# design.net
KiCad netlist of a schematic drawn in Altium Designer
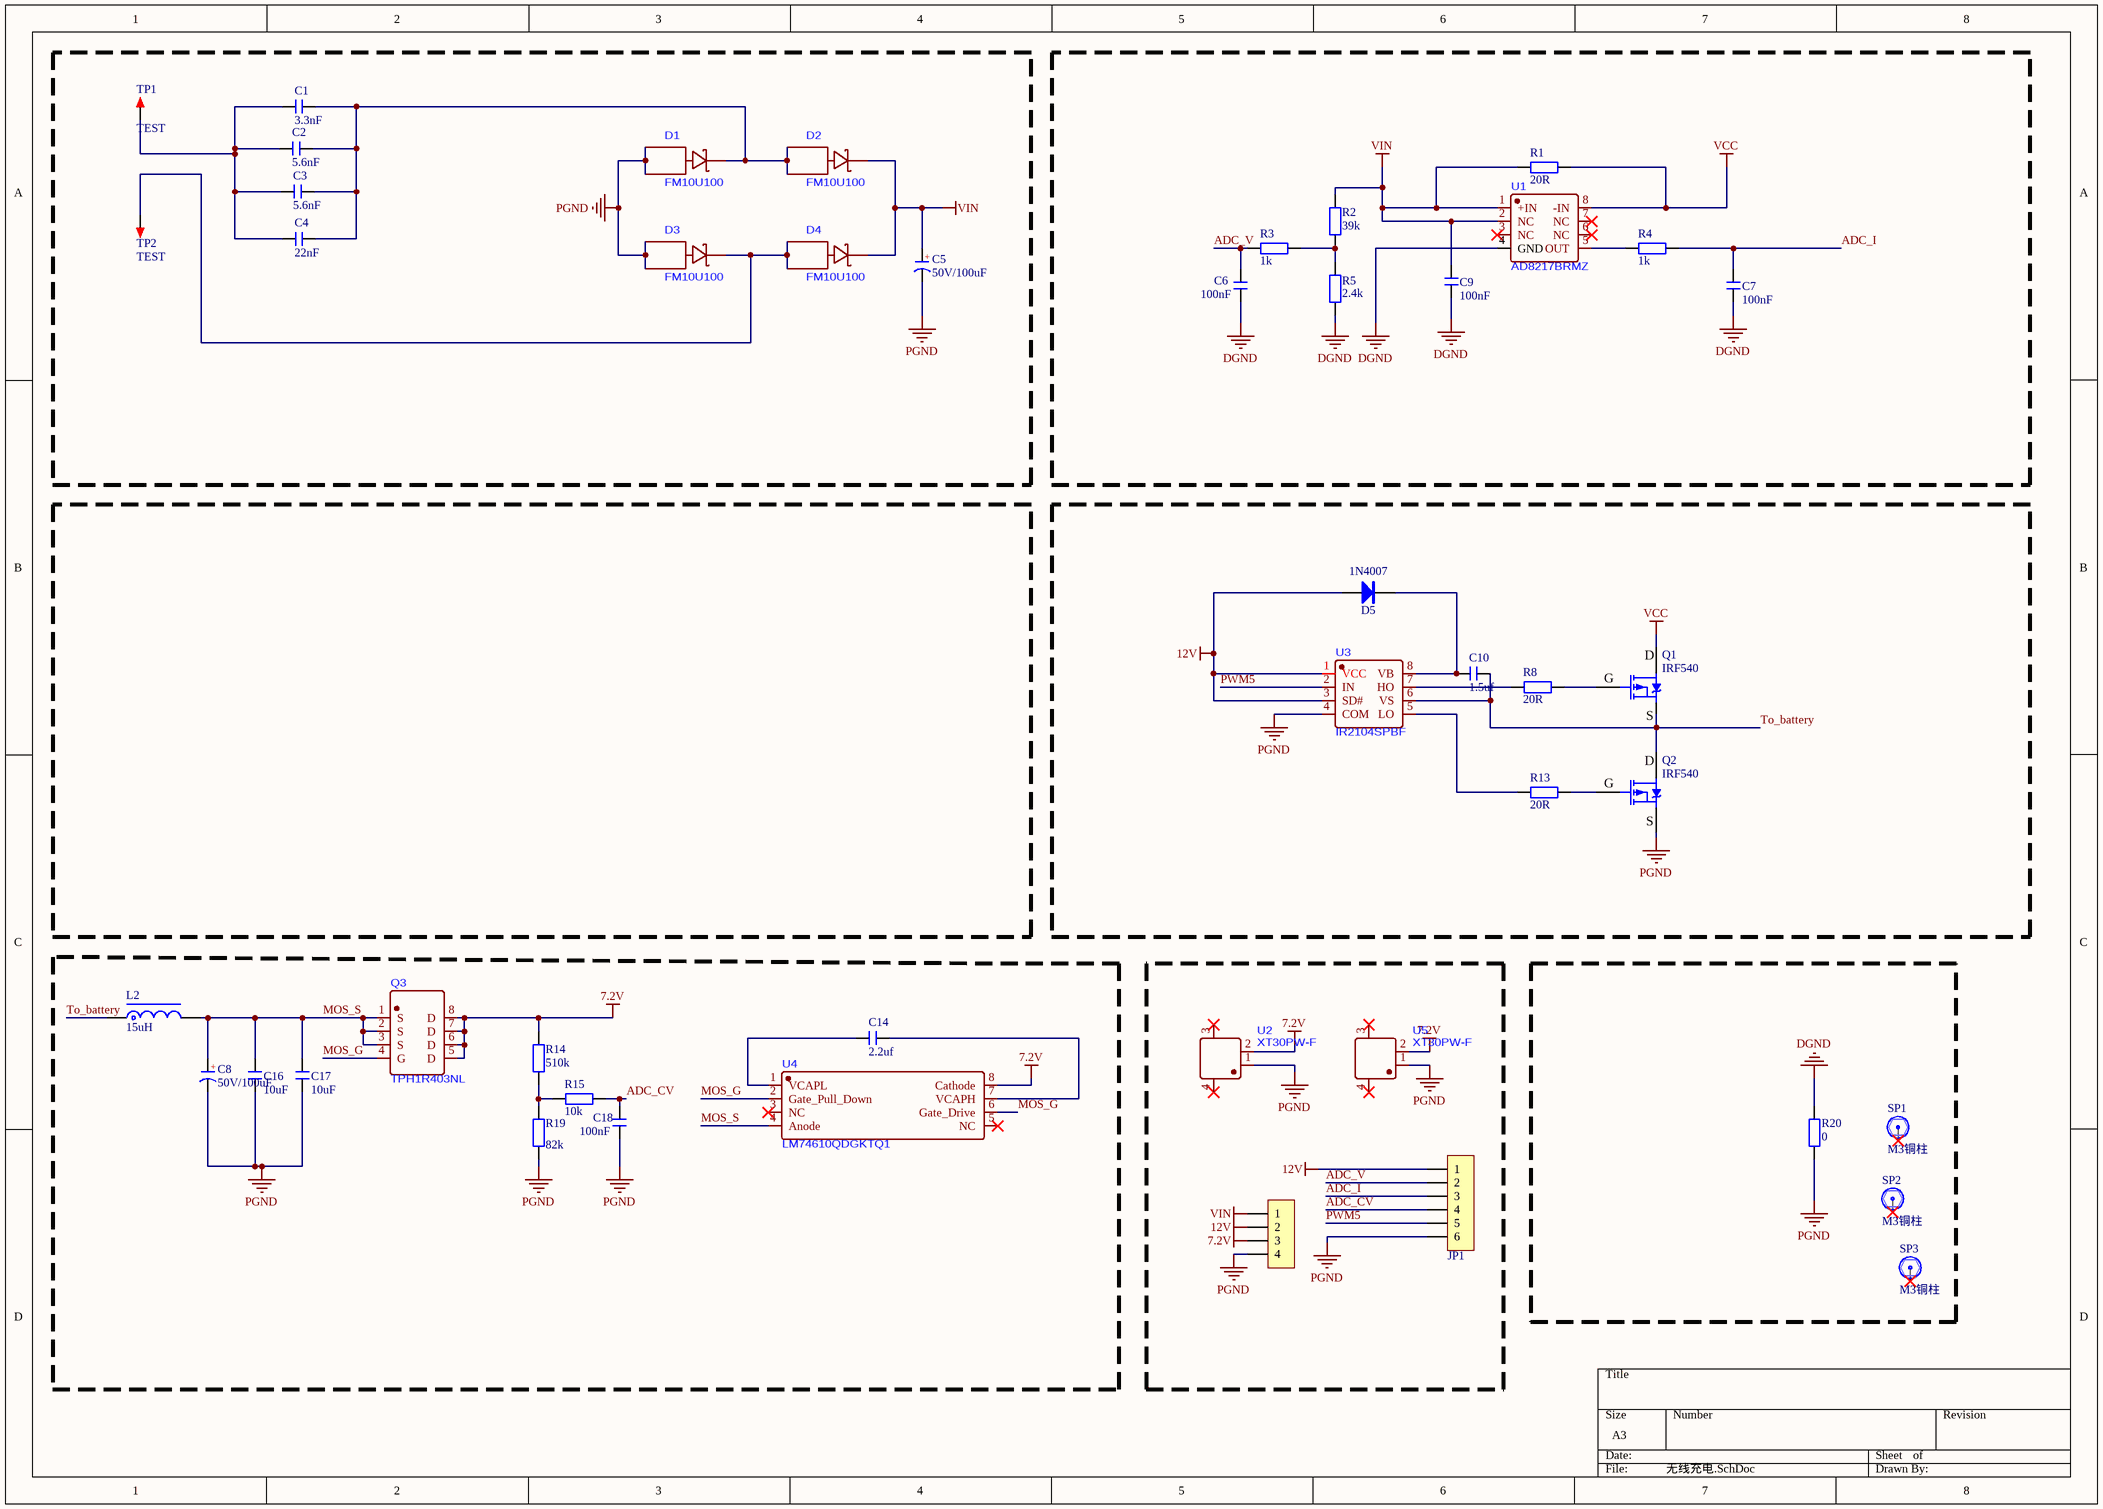
[diagram p0: 无线充电.SchDoc]

(export (version "E")
  (design (tool "Eeschema 10.0.6"))
  (components
    (comp (ref "C1")
      (value "3.3nF")
      (footprint "C 1210_M")
      (description "无极性贴片电容")
      (fields (field (name "Comment") "C") (field (name "版权归属") "电协硬件组"))
      (libsource (lib "3.1   - 电阻-电容-电感") (part "C"))
    )
    (comp (ref "C2")
      (value "5.6nF")
      (footprint "C 1210_M")
      (description "无极性贴片电容")
      (fields (field (name "Comment") "C") (field (name "版权归属") "电协硬件组"))
      (libsource (lib "3.1   - 电阻-电容-电感") (part "C"))
    )
    (comp (ref "C3")
      (value "5.6nF")
      (footprint "C 1210_M")
      (description "无极性贴片电容")
      (fields (field (name "Comment") "C") (field (name "版权归属") "电协硬件组"))
      (libsource (lib "3.1   - 电阻-电容-电感") (part "C"))
    )
    (comp (ref "C4")
      (value "22nF")
      (footprint "C 1210_M")
      (description "无极性贴片电容")
      (fields (field (name "Comment") "C") (field (name "版权归属") "电协硬件组"))
      (libsource (lib "3.1   - 电阻-电容-电感") (part "C"))
    )
    (comp (ref "C5")
      (value "50V/100uF")
      (footprint "CM E(8*10.2)")
      (description "贴片电解电容")
      (fields (field (name "Comment") "C-CM") (field (name "版权归属") "电协硬件组"))
      (libsource (lib "3.1   - 电阻-电容-电感") (part "C-CM"))
    )
    (comp (ref "C6")
      (value "100nF")
      (footprint "C 0603_M")
      (description "无极性贴片电容")
      (fields (field (name "Comment") "C") (field (name "版权归属") "电协硬件组"))
      (libsource (lib "3.1   - 电阻-电容-电感") (part "C"))
    )
    (comp (ref "C7")
      (value "100nF")
      (footprint "C 0603_M")
      (description "无极性贴片电容")
      (fields (field (name "Comment") "C") (field (name "版权归属") "电协硬件组"))
      (libsource (lib "3.1   - 电阻-电容-电感") (part "C"))
    )
    (comp (ref "C8")
      (value "50V/100uF")
      (footprint "CM E(8*10.2)")
      (description "贴片电解电容")
      (fields (field (name "Comment") "C-CM") (field (name "版权归属") "电协硬件组"))
      (libsource (lib "3.1   - 电阻-电容-电感") (part "C-CM"))
    )
    (comp (ref "C9")
      (value "100nF")
      (footprint "C 0603_M")
      (description "无极性贴片电容")
      (fields (field (name "Comment") "C") (field (name "版权归属") "电协硬件组"))
      (libsource (lib "3.1   - 电阻-电容-电感") (part "C"))
    )
    (comp (ref "C10")
      (value "1.5uf")
      (footprint "C 0603")
      (description "无极性贴片电容")
      (fields (field (name "版权归属") "源创客"))
      (libsource (lib "电阻-电容-电感") (part "C"))
    )
    (comp (ref "C14")
      (value "2.2uf")
      (footprint "C 0603")
      (description "无极性贴片电容")
      (fields (field (name "版权归属") "源创客"))
      (libsource (lib "电阻-电容-电感") (part "C"))
    )
    (comp (ref "C16")
      (value "10uF")
      (footprint "C 1210_M")
      (description "无极性贴片电容")
      (fields (field (name "Comment") "C") (field (name "版权归属") "电协硬件组"))
      (libsource (lib "3.1   - 电阻-电容-电感") (part "C"))
    )
    (comp (ref "C17")
      (value "10uF")
      (footprint "C 1210_M")
      (description "无极性贴片电容")
      (fields (field (name "Comment") "C") (field (name "版权归属") "电协硬件组"))
      (libsource (lib "3.1   - 电阻-电容-电感") (part "C"))
    )
    (comp (ref "C18")
      (value "100nF")
      (footprint "C 0603_M")
      (description "无极性贴片电容")
      (fields (field (name "Comment") "C") (field (name "版权归属") "电协硬件组"))
      (libsource (lib "3.1   - 电阻-电容-电感") (part "C"))
    )
    (comp (ref "D1")
      (value "FM10U100")
      (footprint "TO-277B_3P-L6.1-W4.3-LS7.0-TR")
      (libsource (lib "FM10U100") (part "FM10U100"))
    )
    (comp (ref "D2")
      (value "FM10U100")
      (footprint "TO-277B_3P-L6.1-W4.3-LS7.0-TR")
      (libsource (lib "FM10U100") (part "FM10U100"))
    )
    (comp (ref "D3")
      (value "FM10U100")
      (footprint "TO-277B_3P-L6.1-W4.3-LS7.0-TR")
      (libsource (lib "FM10U100") (part "FM10U100"))
    )
    (comp (ref "D4")
      (value "FM10U100")
      (footprint "TO-277B_3P-L6.1-W4.3-LS7.0-TR")
      (libsource (lib "FM10U100") (part "FM10U100"))
    )
    (comp (ref "D5")
      (value "1N4007")
      (footprint "SMA")
      (description "肖特基二极管")
      (fields (field (name "版权归属") "电协硬件组"))
      (libsource (lib "8.1   - 二极管-整流桥") (part "SS14"))
    )
    (comp (ref "JP1")
      (value "HDR-1X6")
      (footprint "XH2.54-WI-6P")
      (description "6P接插件")
      (fields (field (name "版权归属") "源创客"))
      (libsource (lib "4.5   - 接插件-脚距2.54") (part "Header 6"))
    )
    (comp (ref "L2")
      (value "15uH")
      (footprint "CD104")
      (description "贴片功率电感")
      (fields (field (name "Comment") "L-CD") (field (name "版权归属") "电协硬件组"))
      (libsource (lib "3.1   - 电阻-电容-电感") (part "L-CD"))
    )
    (comp (ref "Q1")
      (value "IRF540")
      (footprint "TO263-3B")
      (description "P沟场效应管")
      (fields (field (name "版权归属") "电协硬件组"))
      (libsource (lib "6.1   - 场效应管-可控硅") (part "IRF540"))
    )
    (comp (ref "Q2")
      (value "IRF540")
      (footprint "TO263-3B")
      (description "P沟场效应管")
      (fields (field (name "版权归属") "电协硬件组"))
      (libsource (lib "6.1   - 场效应管-可控硅") (part "IRF540"))
    )
    (comp (ref "Q3")
      (value "TPH1R403NL")
      (footprint "DSOP-8_L5.0-W5.0-P1.27-EP-TL")
      (libsource (lib "TPH1R403NL") (part "TPH1R403NL"))
    )
    (comp (ref "R1")
      (value "20R")
      (footprint "R 2512_M")
      (description "贴片电阻")
      (fields (field (name "Comment") "R") (field (name "版权归属") "电协硬件组"))
      (libsource (lib "3.1   - 电阻-电容-电感") (part "R"))
    )
    (comp (ref "R2")
      (value "39k")
      (footprint "R 0603_M")
      (description "贴片电阻")
      (fields (field (name "Comment") "R") (field (name "版权归属") "电协硬件组"))
      (libsource (lib "3.1   - 电阻-电容-电感") (part "R"))
    )
    (comp (ref "R3")
      (value "1k")
      (footprint "R 0603_M")
      (description "贴片电阻")
      (fields (field (name "Comment") "R") (field (name "版权归属") "电协硬件组"))
      (libsource (lib "3.1   - 电阻-电容-电感") (part "R"))
    )
    (comp (ref "R4")
      (value "1k")
      (footprint "R 0603_M")
      (description "贴片电阻")
      (fields (field (name "Comment") "R") (field (name "版权归属") "电协硬件组"))
      (libsource (lib "3.1   - 电阻-电容-电感") (part "R"))
    )
    (comp (ref "R5")
      (value "2.4k")
      (footprint "R 0603_M")
      (description "贴片电阻")
      (fields (field (name "Comment") "R") (field (name "版权归属") "电协硬件组"))
      (libsource (lib "3.1   - 电阻-电容-电感") (part "R"))
    )
    (comp (ref "R8")
      (value "20R")
      (footprint "R 0603")
      (description "贴片电阻")
      (fields (field (name "版权归属") "源创客"))
      (libsource (lib "电阻-电容-电感") (part "R"))
    )
    (comp (ref "R13")
      (value "20R")
      (footprint "R 0603")
      (description "贴片电阻")
      (fields (field (name "版权归属") "源创客"))
      (libsource (lib "电阻-电容-电感") (part "R"))
    )
    (comp (ref "R14")
      (value "510k")
      (footprint "R 0603_M")
      (description "贴片电阻")
      (fields (field (name "Comment") "R") (field (name "版权归属") "电协硬件组"))
      (libsource (lib "3.1   - 电阻-电容-电感") (part "R"))
    )
    (comp (ref "R15")
      (value "10k")
      (footprint "R 0603_M")
      (description "贴片电阻")
      (fields (field (name "Comment") "R") (field (name "版权归属") "电协硬件组"))
      (libsource (lib "3.1   - 电阻-电容-电感") (part "R"))
    )
    (comp (ref "R19")
      (value "82k")
      (footprint "R 0603_M")
      (description "贴片电阻")
      (fields (field (name "Comment") "R") (field (name "版权归属") "电协硬件组"))
      (libsource (lib "3.1   - 电阻-电容-电感") (part "R"))
    )
    (comp (ref "R20")
      (value "0")
      (footprint "R 1206_L")
      (description "贴片电阻")
      (fields (field (name "Comment") "R") (field (name "版权归属") "电协硬件组"))
      (libsource (lib "3.1   - 电阻-电容-电感") (part "R"))
    )
    (comp (ref "SP1")
      (value "M3铜柱")
      (footprint "M3x4_L")
      (description "铜柱")
      (fields (field (name "版权归属") "电协硬件组"))
      (libsource (lib "15.1 - 未分类器件") (part "铜柱小焊盘"))
    )
    (comp (ref "SP2")
      (value "M3铜柱")
      (footprint "M3x4_L")
      (description "铜柱")
      (fields (field (name "版权归属") "电协硬件组"))
      (libsource (lib "15.1 - 未分类器件") (part "铜柱小焊盘"))
    )
    (comp (ref "SP3")
      (value "M3铜柱")
      (footprint "M3x4_L")
      (description "铜柱")
      (fields (field (name "版权归属") "电协硬件组"))
      (libsource (lib "15.1 - 未分类器件") (part "铜柱小焊盘"))
    )
    (comp (ref "test1")
      (value "HDR-1X4")
      (footprint "HDR2.54-LI-4P")
      (description "4P接插件")
      (fields (field (name "版权归属") "源创客"))
      (libsource (lib "4.5   - 接插件-脚距2.54") (part "Header 4"))
    )
    (comp (ref "TP1")
      (value "TEST")
      (footprint "TEST 1.6")
      (description "测试点")
      (fields (field (name "版权归属") "电协硬件组"))
      (libsource (lib "15.1 - 未分类器件") (part "TEST"))
    )
    (comp (ref "TP2")
      (value "TEST")
      (footprint "TEST 1.6")
      (description "测试点")
      (fields (field (name "版权归属") "电协硬件组"))
      (libsource (lib "15.1 - 未分类器件") (part "TEST"))
    )
    (comp (ref "U1")
      (value "AD8217BRMZ")
      (footprint "MSOP-8_L3.0-W3.0-P0.65-LS4.9-BL")
      (libsource (lib "无线充电小合集") (part "AD8217BRMZ"))
    )
    (comp (ref "U2")
      (value "XT30PW-F")
      (footprint "CONN-TH_XT30PW-F")
      (libsource (lib "主控") (part "XT30PW-F"))
    )
    (comp (ref "U3")
      (value "IR2104SPBF")
      (footprint "SOIC-8_L5.0-W4.0-P1.27-LS6.0-BL")
      (libsource (lib "IR2014") (part "IR2104SPBF"))
    )
    (comp (ref "U4")
      (value "LM74610QDGKTQ1")
      (footprint "VSSOP-8_L3.0-W3.0-P0.65-LS5.0-BL")
      (libsource (lib "无线充电小合集") (part "LM74610QDGKTQ1"))
    )
    (comp (ref "U5")
      (value "XT30PW-F")
      (footprint "CONN-TH_XT30PW-F")
      (libsource (lib "主控") (part "XT30PW-F"))
    )
  )
  (nets
    (net (code "1") (name "/ADC_CV") (class "Default")
      (node (ref "C18") (pin "2") (pinfunction "2_2") (pintype "passive"))
      (node (ref "JP1") (pin "4") (pinfunction "4_4") (pintype "passive"))
      (node (ref "R15") (pin "1") (pinfunction "1_1") (pintype "passive"))
    )
    (net (code "2") (name "/ADC_I") (class "Default")
      (node (ref "C7") (pin "2") (pinfunction "2_2") (pintype "passive"))
      (node (ref "JP1") (pin "3") (pinfunction "3_3") (pintype "passive"))
      (node (ref "R4") (pin "2") (pinfunction "2_2") (pintype "passive"))
    )
    (net (code "3") (name "/ADC_V") (class "Default")
      (node (ref "C6") (pin "2") (pinfunction "2_2") (pintype "passive"))
      (node (ref "JP1") (pin "2") (pinfunction "2_2") (pintype "passive"))
      (node (ref "R3") (pin "2") (pinfunction "2_2") (pintype "passive"))
    )
    (net (code "4") (name "/MOS_G") (class "Default")
      (node (ref "Q3") (pin "4") (pinfunction "G_4") (pintype "passive"))
      (node (ref "U4") (pin "2") (pinfunction "Gate_Pull_Down_2") (pintype "passive"))
      (node (ref "U4") (pin "6") (pinfunction "Gate_Drive_6") (pintype "passive"))
    )
    (net (code "5") (name "/MOS_S") (class "Default")
      (node (ref "C16") (pin "2") (pinfunction "2_2") (pintype "passive"))
      (node (ref "C17") (pin "2") (pinfunction "2_2") (pintype "passive"))
      (node (ref "C8") (pin "1") (pinfunction "A_1") (pintype "passive"))
      (node (ref "L2") (pin "2") (pinfunction "2_2") (pintype "passive"))
      (node (ref "Q3") (pin "1") (pinfunction "S_1") (pintype "passive"))
      (node (ref "Q3") (pin "2") (pinfunction "S_2") (pintype "passive"))
      (node (ref "Q3") (pin "3") (pinfunction "S_3") (pintype "passive"))
      (node (ref "U4") (pin "4") (pinfunction "Anode_4") (pintype "passive"))
    )
    (net (code "6") (name "/PWM5") (class "Default")
      (node (ref "JP1") (pin "5") (pinfunction "5_5") (pintype "passive"))
      (node (ref "U3") (pin "2") (pinfunction "IN_2") (pintype "passive"))
    )
    (net (code "7") (name "/To_battery") (class "Default")
      (node (ref "C10") (pin "2") (pinfunction "2_2") (pintype "passive"))
      (node (ref "L2") (pin "1") (pinfunction "1_1") (pintype "passive"))
      (node (ref "Q1") (pin "3") (pinfunction "S_3") (pintype "passive"))
      (node (ref "Q2") (pin "2") (pinfunction "D_2") (pintype "passive"))
      (node (ref "U3") (pin "6") (pinfunction "VS_6") (pintype "passive"))
    )
    (net (code "8") (name "7.2V") (class "Default")
      (node (ref "Q3") (pin "5") (pinfunction "D_5") (pintype "passive"))
      (node (ref "Q3") (pin "6") (pinfunction "D_6") (pintype "passive"))
      (node (ref "Q3") (pin "7") (pinfunction "D_7") (pintype "passive"))
      (node (ref "Q3") (pin "8") (pinfunction "D_8") (pintype "passive"))
      (node (ref "R14") (pin "2") (pinfunction "2_2") (pintype "passive"))
      (node (ref "U2") (pin "2") (pinfunction "2_2") (pintype "passive"))
      (node (ref "U4") (pin "8") (pinfunction "Cathode_8") (pintype "passive"))
      (node (ref "U5") (pin "2") (pinfunction "2_2") (pintype "passive"))
      (node (ref "test1") (pin "3") (pinfunction "3_3") (pintype "passive"))
    )
    (net (code "9") (name "12V") (class "Default")
      (node (ref "D5") (pin "1") (pinfunction "A_1") (pintype "passive"))
      (node (ref "JP1") (pin "1") (pinfunction "1_1") (pintype "passive"))
      (node (ref "U3") (pin "1") (pinfunction "VCC_1") (pintype "passive"))
      (node (ref "U3") (pin "3") (pinfunction "SD#_3") (pintype "passive"))
      (node (ref "test1") (pin "2") (pinfunction "2_2") (pintype "passive"))
    )
    (net (code "10") (name "DGND") (class "Default")
      (node (ref "C6") (pin "1") (pinfunction "1_1") (pintype "passive"))
      (node (ref "C7") (pin "1") (pinfunction "1_1") (pintype "passive"))
      (node (ref "C9") (pin "2") (pinfunction "2_2") (pintype "passive"))
      (node (ref "R20") (pin "1") (pinfunction "1_1") (pintype "passive"))
      (node (ref "R5") (pin "1") (pinfunction "1_1") (pintype "passive"))
      (node (ref "U1") (pin "4") (pinfunction "GND_4") (pintype "passive"))
    )
    (net (code "11") (name "Net-(C1-Pad1)") (class "Default")
      (node (ref "C1") (pin "1") (pinfunction "1_1") (pintype "passive"))
      (node (ref "C2") (pin "1") (pinfunction "1_1") (pintype "passive"))
      (node (ref "C3") (pin "1") (pinfunction "1_1") (pintype "passive"))
      (node (ref "C4") (pin "1") (pinfunction "1_1") (pintype "passive"))
      (node (ref "TP1") (pin "1") (pinfunction "1_1") (pintype "passive"))
    )
    (net (code "12") (name "Net-(D1-C)") (class "Default")
      (node (ref "C1") (pin "2") (pinfunction "2_2") (pintype "passive"))
      (node (ref "C2") (pin "2") (pinfunction "2_2") (pintype "passive"))
      (node (ref "C3") (pin "2") (pinfunction "2_2") (pintype "passive"))
      (node (ref "C4") (pin "2") (pinfunction "2_2") (pintype "passive"))
      (node (ref "D1") (pin "2") (pinfunction "C_2") (pintype "passive"))
      (node (ref "D2") (pin "1") (pinfunction "A_1") (pintype "passive"))
      (node (ref "D2") (pin "3") (pinfunction "A_3") (pintype "passive"))
    )
    (net (code "13") (name "Net-(D3-C)") (class "Default")
      (node (ref "D3") (pin "2") (pinfunction "C_2") (pintype "passive"))
      (node (ref "D4") (pin "1") (pinfunction "A_1") (pintype "passive"))
      (node (ref "D4") (pin "3") (pinfunction "A_3") (pintype "passive"))
      (node (ref "TP2") (pin "1") (pinfunction "1_1") (pintype "passive"))
    )
    (net (code "14") (name "Net-(D5-K)") (class "Default")
      (node (ref "C10") (pin "1") (pinfunction "1_1") (pintype "passive"))
      (node (ref "D5") (pin "2") (pinfunction "K_2") (pintype "passive"))
      (node (ref "U3") (pin "8") (pinfunction "VB_8") (pintype "passive"))
    )
    (net (code "15") (name "Net-(Q1-G)") (class "Default")
      (node (ref "Q1") (pin "1") (pinfunction "G_1") (pintype "passive"))
      (node (ref "R8") (pin "2") (pinfunction "2_2") (pintype "passive"))
    )
    (net (code "16") (name "Net-(Q2-G)") (class "Default")
      (node (ref "Q2") (pin "1") (pinfunction "G_1") (pintype "passive"))
      (node (ref "R13") (pin "2") (pinfunction "2_2") (pintype "passive"))
    )
    (net (code "17") (name "Net-(R2-Pad1)") (class "Default")
      (node (ref "R2") (pin "1") (pinfunction "1_1") (pintype "passive"))
      (node (ref "R3") (pin "1") (pinfunction "1_1") (pintype "passive"))
      (node (ref "R5") (pin "2") (pinfunction "2_2") (pintype "passive"))
    )
    (net (code "18") (name "Net-(R14-Pad1)") (class "Default")
      (node (ref "R14") (pin "1") (pinfunction "1_1") (pintype "passive"))
      (node (ref "R15") (pin "2") (pinfunction "2_2") (pintype "passive"))
      (node (ref "R19") (pin "2") (pinfunction "2_2") (pintype "passive"))
    )
    (net (code "19") (name "Net-(U1-OUT)") (class "Default")
      (node (ref "R4") (pin "1") (pinfunction "1_1") (pintype "passive"))
      (node (ref "U1") (pin "5") (pinfunction "OUT_5") (pintype "passive"))
    )
    (net (code "20") (name "Net-(U3-HO)") (class "Default")
      (node (ref "R8") (pin "1") (pinfunction "1_1") (pintype "passive"))
      (node (ref "U3") (pin "7") (pinfunction "HO_7") (pintype "passive"))
    )
    (net (code "21") (name "Net-(U3-LO)") (class "Default")
      (node (ref "R13") (pin "1") (pinfunction "1_1") (pintype "passive"))
      (node (ref "U3") (pin "5") (pinfunction "LO_5") (pintype "passive"))
    )
    (net (code "22") (name "Net-(U4-VCAPH)") (class "Default")
      (node (ref "C14") (pin "2") (pinfunction "2_2") (pintype "passive"))
      (node (ref "U4") (pin "7") (pinfunction "VCAPH_7") (pintype "passive"))
    )
    (net (code "23") (name "Net-(U4-VCAPL)") (class "Default")
      (node (ref "C14") (pin "1") (pinfunction "1_1") (pintype "passive"))
      (node (ref "U4") (pin "1") (pinfunction "VCAPL_1") (pintype "passive"))
    )
    (net (code "24") (name "PGND") (class "Default")
      (node (ref "C16") (pin "1") (pinfunction "1_1") (pintype "passive"))
      (node (ref "C17") (pin "1") (pinfunction "1_1") (pintype "passive"))
      (node (ref "C18") (pin "1") (pinfunction "1_1") (pintype "passive"))
      (node (ref "C5") (pin "2") (pinfunction "K_2") (pintype "passive"))
      (node (ref "C8") (pin "2") (pinfunction "K_2") (pintype "passive"))
      (node (ref "D1") (pin "1") (pinfunction "A_1") (pintype "passive"))
      (node (ref "D1") (pin "3") (pinfunction "A_3") (pintype "passive"))
      (node (ref "D3") (pin "1") (pinfunction "A_1") (pintype "passive"))
      (node (ref "D3") (pin "3") (pinfunction "A_3") (pintype "passive"))
      (node (ref "JP1") (pin "6") (pinfunction "6_6") (pintype "passive"))
      (node (ref "Q2") (pin "3") (pinfunction "S_3") (pintype "passive"))
      (node (ref "R19") (pin "1") (pinfunction "1_1") (pintype "passive"))
      (node (ref "R20") (pin "2") (pinfunction "2_2") (pintype "passive"))
      (node (ref "U2") (pin "1") (pinfunction "1_1") (pintype "passive"))
      (node (ref "U3") (pin "4") (pinfunction "COM_4") (pintype "passive"))
      (node (ref "U5") (pin "1") (pinfunction "1_1") (pintype "passive"))
      (node (ref "test1") (pin "4") (pinfunction "4_4") (pintype "passive"))
    )
    (net (code "25") (name "VCC") (class "Default")
      (node (ref "Q1") (pin "2") (pinfunction "D_2") (pintype "passive"))
      (node (ref "R1") (pin "2") (pinfunction "2_2") (pintype "passive"))
      (node (ref "U1") (pin "8") (pinfunction "-IN_8") (pintype "passive"))
    )
    (net (code "26") (name "VIN") (class "Default")
      (node (ref "C5") (pin "1") (pinfunction "A_1") (pintype "passive"))
      (node (ref "C9") (pin "1") (pinfunction "1_1") (pintype "passive"))
      (node (ref "D2") (pin "2") (pinfunction "C_2") (pintype "passive"))
      (node (ref "D4") (pin "2") (pinfunction "C_2") (pintype "passive"))
      (node (ref "R1") (pin "1") (pinfunction "1_1") (pintype "passive"))
      (node (ref "R2") (pin "2") (pinfunction "2_2") (pintype "passive"))
      (node (ref "U1") (pin "1") (pinfunction "+IN_1") (pintype "passive"))
      (node (ref "U1") (pin "2") (pinfunction "NC_2") (pintype "passive"))
      (node (ref "test1") (pin "1") (pinfunction "1_1") (pintype "passive"))
    )
    (net (code "27") (name "unconnected-(SP1-Pad1)") (class "Default")
      (node (ref "SP1") (pin "1") (pinfunction "1_1") (pintype "passive+no_connect"))
    )
    (net (code "28") (name "unconnected-(SP2-Pad1)") (class "Default")
      (node (ref "SP2") (pin "1") (pinfunction "1_1") (pintype "passive+no_connect"))
    )
    (net (code "29") (name "unconnected-(SP3-Pad1)") (class "Default")
      (node (ref "SP3") (pin "1") (pinfunction "1_1") (pintype "passive+no_connect"))
    )
    (net (code "30") (name "unconnected-(U1-NC-Pad3)") (class "Default")
      (node (ref "U1") (pin "3") (pinfunction "NC_3") (pintype "passive+no_connect"))
    )
    (net (code "31") (name "unconnected-(U1-NC-Pad6)") (class "Default")
      (node (ref "U1") (pin "6") (pinfunction "NC_6") (pintype "passive+no_connect"))
    )
    (net (code "32") (name "unconnected-(U1-NC-Pad7)") (class "Default")
      (node (ref "U1") (pin "7") (pinfunction "NC_7") (pintype "passive+no_connect"))
    )
    (net (code "33") (name "unconnected-(U2-Pad3)") (class "Default")
      (node (ref "U2") (pin "3") (pinfunction "3_3") (pintype "passive+no_connect"))
    )
    (net (code "34") (name "unconnected-(U2-Pad4)") (class "Default")
      (node (ref "U2") (pin "4") (pinfunction "4_4") (pintype "passive+no_connect"))
    )
    (net (code "35") (name "unconnected-(U4-NC-Pad3)") (class "Default")
      (node (ref "U4") (pin "3") (pinfunction "NC_3") (pintype "passive+no_connect"))
    )
    (net (code "36") (name "unconnected-(U4-NC-Pad5)") (class "Default")
      (node (ref "U4") (pin "5") (pinfunction "NC_5") (pintype "passive+no_connect"))
    )
    (net (code "37") (name "unconnected-(U5-Pad3)") (class "Default")
      (node (ref "U5") (pin "3") (pinfunction "3_3") (pintype "passive+no_connect"))
    )
    (net (code "38") (name "unconnected-(U5-Pad4)") (class "Default")
      (node (ref "U5") (pin "4") (pinfunction "4_4") (pintype "passive+no_connect"))
    )
  )
)
